# throwing_star.net
KiCad netlist of a schematic drawn in EAGLE
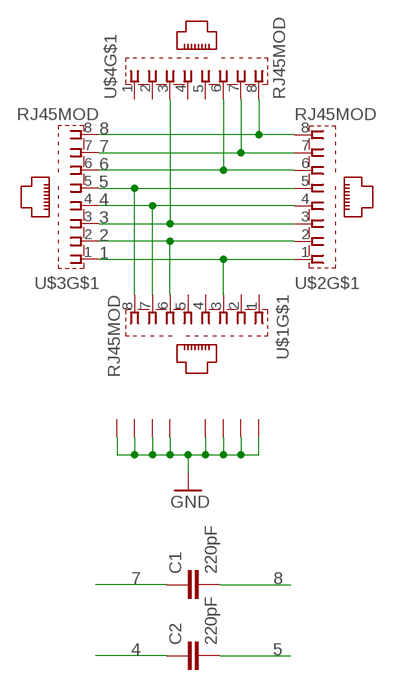
[diagram p0: schematic, sheet 1]

(export (version "E")
  (design (tool "Eeschema 10.0.6"))
  (components
    (comp (ref "C1")
      (value "220pF")
      (footprint "eagle-import:C050-024X044")
      (libsource (lib "eagle-import") (part "C-EU050-024X044"))
    )
    (comp (ref "C2")
      (value "220pF")
      (footprint "eagle-import:C050-024X044")
      (libsource (lib "eagle-import") (part "C-EU050-024X044"))
    )
    (comp (ref "U$1")
      (value "RJ45MOD")
      (footprint "eagle-import:RJ45MOD")
      (libsource (lib "eagle-import") (part "RJ45MOD"))
    )
    (comp (ref "U$2")
      (value "RJ45MOD")
      (footprint "eagle-import:RJ45MOD")
      (libsource (lib "eagle-import") (part "RJ45MOD"))
    )
    (comp (ref "U$3")
      (value "RJ45MOD")
      (footprint "eagle-import:RJ45MOD")
      (libsource (lib "eagle-import") (part "RJ45MOD"))
    )
    (comp (ref "U$4")
      (value "RJ45MOD")
      (footprint "eagle-import:RJ45MOD")
      (libsource (lib "eagle-import") (part "RJ45MOD"))
    )
  )
  (nets
    (net (code "1") (name "/1") (class "Default")
      (node (ref "U$1") (pin "3") (pinfunction "3_3") (pintype "passive"))
      (node (ref "U$2") (pin "1") (pinfunction "1_1") (pintype "passive"))
      (node (ref "U$3") (pin "1") (pinfunction "1_1") (pintype "passive"))
    )
    (net (code "2") (name "/2") (class "Default")
      (node (ref "U$1") (pin "6") (pinfunction "6_6") (pintype "passive"))
      (node (ref "U$2") (pin "2") (pinfunction "2_2") (pintype "passive"))
      (node (ref "U$3") (pin "2") (pinfunction "2_2") (pintype "passive"))
    )
    (net (code "3") (name "/3") (class "Default")
      (node (ref "U$2") (pin "3") (pinfunction "3_3") (pintype "passive"))
      (node (ref "U$3") (pin "3") (pinfunction "3_3") (pintype "passive"))
      (node (ref "U$4") (pin "3") (pinfunction "3_3") (pintype "passive"))
    )
    (net (code "4") (name "/4") (class "Default")
      (node (ref "C2") (pin "1") (pinfunction "1_1") (pintype "passive"))
      (node (ref "U$1") (pin "7") (pinfunction "7_7") (pintype "passive"))
      (node (ref "U$2") (pin "4") (pinfunction "4_4") (pintype "passive"))
      (node (ref "U$3") (pin "4") (pinfunction "4_4") (pintype "passive"))
    )
    (net (code "5") (name "/5") (class "Default")
      (node (ref "C2") (pin "2") (pinfunction "2_2") (pintype "passive"))
      (node (ref "U$1") (pin "8") (pinfunction "8_8") (pintype "passive"))
      (node (ref "U$2") (pin "5") (pinfunction "5_5") (pintype "passive"))
      (node (ref "U$3") (pin "5") (pinfunction "5_5") (pintype "passive"))
    )
    (net (code "6") (name "/6") (class "Default")
      (node (ref "U$2") (pin "6") (pinfunction "6_6") (pintype "passive"))
      (node (ref "U$3") (pin "6") (pinfunction "6_6") (pintype "passive"))
      (node (ref "U$4") (pin "6") (pinfunction "6_6") (pintype "passive"))
    )
    (net (code "7") (name "/7") (class "Default")
      (node (ref "C1") (pin "1") (pinfunction "1_1") (pintype "passive"))
      (node (ref "U$2") (pin "7") (pinfunction "7_7") (pintype "passive"))
      (node (ref "U$3") (pin "7") (pinfunction "7_7") (pintype "passive"))
      (node (ref "U$4") (pin "7") (pinfunction "7_7") (pintype "passive"))
    )
    (net (code "8") (name "/8") (class "Default")
      (node (ref "C1") (pin "2") (pinfunction "2_2") (pintype "passive"))
      (node (ref "U$2") (pin "8") (pinfunction "8_8") (pintype "passive"))
      (node (ref "U$3") (pin "8") (pinfunction "8_8") (pintype "passive"))
      (node (ref "U$4") (pin "8") (pinfunction "8_8") (pintype "passive"))
    )
    (net (code "9") (name "GND") (class "Default")
      (node (ref "U$1") (pin "G3") (pinfunction "1_G3") (pintype "passive"))
      (node (ref "U$1") (pin "G4") (pinfunction "1_G4") (pintype "passive"))
      (node (ref "U$2") (pin "G3") (pinfunction "1_G3") (pintype "passive"))
      (node (ref "U$2") (pin "G4") (pinfunction "1_G4") (pintype "passive"))
      (node (ref "U$3") (pin "G3") (pinfunction "1_G3") (pintype "passive"))
      (node (ref "U$3") (pin "G4") (pinfunction "1_G4") (pintype "passive"))
      (node (ref "U$4") (pin "G3") (pinfunction "1_G3") (pintype "passive"))
      (node (ref "U$4") (pin "G4") (pinfunction "1_G4") (pintype "passive"))
    )
    (net (code "10") (name "unconnected-(U$1-Pad1)") (class "Default")
      (node (ref "U$1") (pin "1") (pinfunction "1_1") (pintype "passive"))
    )
    (net (code "11") (name "unconnected-(U$1-Pad2)") (class "Default")
      (node (ref "U$1") (pin "2") (pinfunction "2_2") (pintype "passive"))
    )
    (net (code "12") (name "unconnected-(U$1-Pad4)") (class "Default")
      (node (ref "U$1") (pin "4") (pinfunction "4_4") (pintype "passive"))
    )
    (net (code "13") (name "unconnected-(U$1-Pad5)") (class "Default")
      (node (ref "U$1") (pin "5") (pinfunction "5_5") (pintype "passive"))
    )
    (net (code "14") (name "unconnected-(U$4-Pad1)") (class "Default")
      (node (ref "U$4") (pin "1") (pinfunction "1_1") (pintype "passive"))
    )
    (net (code "15") (name "unconnected-(U$4-Pad2)") (class "Default")
      (node (ref "U$4") (pin "2") (pinfunction "2_2") (pintype "passive"))
    )
    (net (code "16") (name "unconnected-(U$4-Pad4)") (class "Default")
      (node (ref "U$4") (pin "4") (pinfunction "4_4") (pintype "passive"))
    )
    (net (code "17") (name "unconnected-(U$4-Pad5)") (class "Default")
      (node (ref "U$4") (pin "5") (pinfunction "5_5") (pintype "passive"))
    )
  )
)
